# Guide_laser.net
KiCad netlist of a schematic drawn in Altium Designer
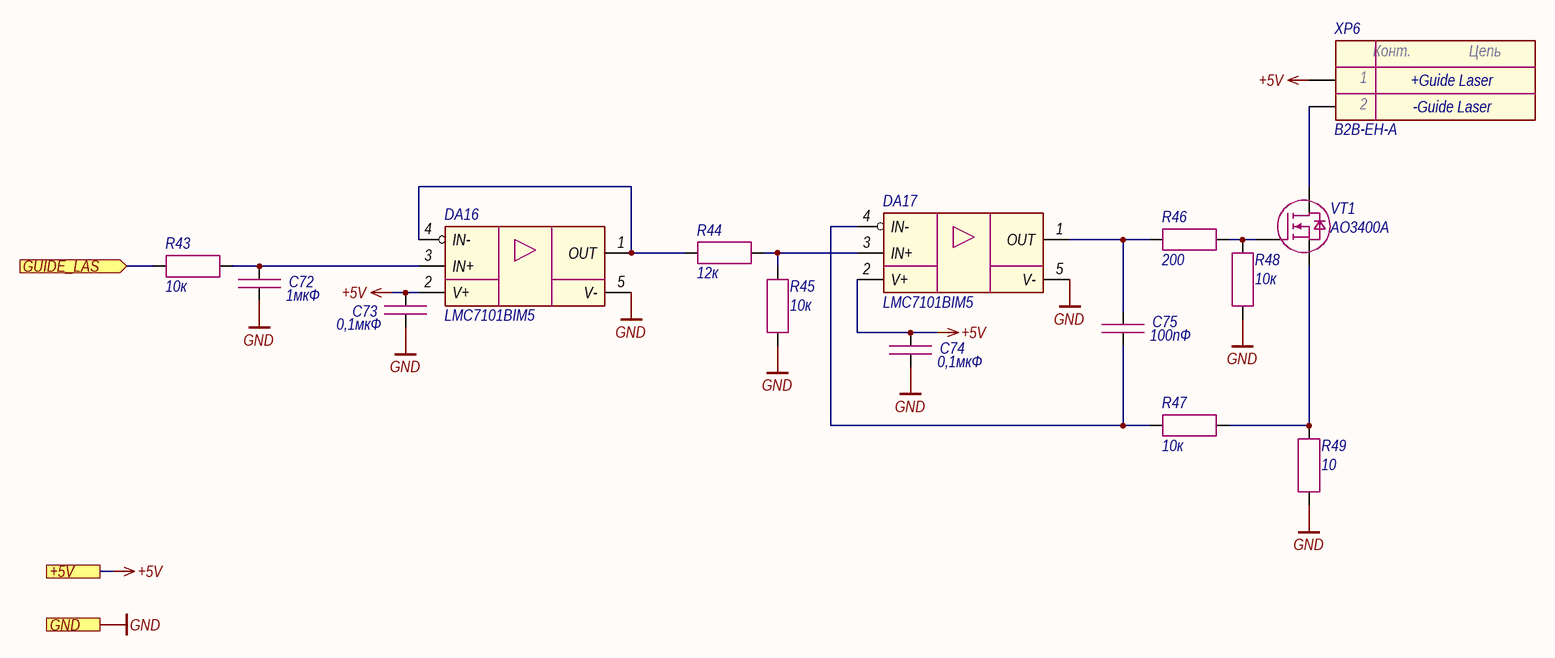
[diagram p0: Guide_laser.SchDoc]

(export (version "E")
  (design (tool "Eeschema 10.0.6"))
  (components
    (comp (ref "C72")
      (value "1мкФ")
      (footprint "Pcb_library:CAP_0603")
      (fields (field (name "MANUFACTURER") "Murata"))
      (libsource (lib "Schem_library") (part "Capacitor"))
    )
    (comp (ref "C73")
      (value "0,1мкФ")
      (footprint "Pcb_library:CAP_0603")
      (fields (field (name "MANUFACTURER") "Murata"))
      (libsource (lib "Schem_library") (part "Capacitor"))
    )
    (comp (ref "C74")
      (value "0,1мкФ")
      (footprint "Pcb_library:CAP_0603")
      (fields (field (name "MANUFACTURER") "Murata"))
      (libsource (lib "Schem_library") (part "Capacitor"))
    )
    (comp (ref "C75")
      (value "100пФ")
      (footprint "Pcb_library:CAP_0603")
      (fields (field (name "MANUFACTURER") "Murata"))
      (libsource (lib "Schem_library") (part "Capacitor"))
    )
    (comp (ref "DA16")
      (value "LMC7101BIM5")
      (footprint "Pcb_library:SOT-23-5")
      (fields (field (name "MANUFACTURER") "Texas Instruments"))
      (libsource (lib "Schem_library") (part "LMC7101"))
    )
    (comp (ref "DA17")
      (value "LMC7101BIM5")
      (footprint "Pcb_library:SOT-23-5")
      (fields (field (name "MANUFACTURER") "Texas Instruments"))
      (libsource (lib "Schem_library") (part "LMC7101"))
    )
    (comp (ref "R43")
      (value "10к")
      (footprint "Pcb_library:RES_0603")
      (fields (field (name "MANUFACTURER") "Yageo"))
      (libsource (lib "Schem_library") (part "Resistor"))
    )
    (comp (ref "R44")
      (value "12к")
      (footprint "Pcb_library:RES_0603")
      (fields (field (name "MANUFACTURER") "Yageo"))
      (libsource (lib "Schem_library") (part "Resistor"))
    )
    (comp (ref "R45")
      (value "10к")
      (footprint "Pcb_library:RES_0603")
      (fields (field (name "MANUFACTURER") "Yageo"))
      (libsource (lib "Schem_library") (part "Resistor"))
    )
    (comp (ref "R46")
      (value "200")
      (footprint "Pcb_library:RES_0603")
      (fields (field (name "MANUFACTURER") "Yageo"))
      (libsource (lib "Schem_library") (part "Resistor"))
    )
    (comp (ref "R47")
      (value "10к")
      (footprint "Pcb_library:RES_0603")
      (fields (field (name "MANUFACTURER") "Yageo"))
      (libsource (lib "Schem_library") (part "Resistor"))
    )
    (comp (ref "R48")
      (value "10к")
      (footprint "Pcb_library:RES_0603")
      (fields (field (name "MANUFACTURER") "Yageo"))
      (libsource (lib "Schem_library") (part "Resistor"))
    )
    (comp (ref "R49")
      (value "10")
      (footprint "Pcb_library:RES_1210")
      (fields (field (name "MANUFACTURER") "Yageo"))
      (libsource (lib "Schem_library") (part "Resistor"))
    )
    (comp (ref "VT1")
      (value "AO3400A")
      (footprint "Pcb_library:SOT-23-3")
      (fields (field (name "MANUFACTURER") "UMW"))
      (libsource (lib "Schem_library") (part "MOSFET N-channel"))
    )
    (comp (ref "XP6")
      (value "B2B-EH-A")
      (footprint "Pcb_library:B2B-EH-A")
      (fields (field (name "MANUFACTURER") "JST"))
      (libsource (lib "Schem_library") (part "Connector-2"))
    )
  )
  (nets
    (net (code "1") (name "+5V") (class "Default")
      (node (ref "C73") (pin "1") (pinfunction "1_1") (pintype "passive"))
      (node (ref "C74") (pin "1") (pinfunction "1_1") (pintype "passive"))
      (node (ref "DA16") (pin "2") (pinfunction "V+_2") (pintype "passive"))
      (node (ref "DA17") (pin "2") (pinfunction "V+_2") (pintype "passive"))
      (node (ref "XP6") (pin "1") (pintype "passive"))
    )
    (net (code "2") (name "/GUIDE_LAS") (class "Default")
      (node (ref "R43") (pin "1") (pinfunction "1_1") (pintype "passive"))
    )
    (net (code "3") (name "GND") (class "Default")
      (node (ref "C72") (pin "2") (pinfunction "2_2") (pintype "passive"))
      (node (ref "C73") (pin "2") (pinfunction "2_2") (pintype "passive"))
      (node (ref "C74") (pin "2") (pinfunction "2_2") (pintype "passive"))
      (node (ref "DA16") (pin "5") (pinfunction "V-_5") (pintype "passive"))
      (node (ref "DA17") (pin "5") (pinfunction "V-_5") (pintype "passive"))
      (node (ref "R45") (pin "2") (pinfunction "2_2") (pintype "passive"))
      (node (ref "R48") (pin "1") (pinfunction "1_1") (pintype "passive"))
      (node (ref "R49") (pin "1") (pinfunction "1_1") (pintype "passive"))
    )
    (net (code "4") (name "Net-(DA16-IN+)") (class "Default")
      (node (ref "C72") (pin "1") (pinfunction "1_1") (pintype "passive"))
      (node (ref "DA16") (pin "3") (pinfunction "IN+_3") (pintype "passive"))
      (node (ref "R43") (pin "2") (pinfunction "2_2") (pintype "passive"))
    )
    (net (code "5") (name "Net-(DA16-IN-)") (class "Default")
      (node (ref "DA16") (pin "1") (pinfunction "OUT_1") (pintype "passive"))
      (node (ref "DA16") (pin "4") (pinfunction "IN-_4") (pintype "passive"))
      (node (ref "R44") (pin "1") (pinfunction "1_1") (pintype "passive"))
    )
    (net (code "6") (name "Net-(DA17-IN+)") (class "Default")
      (node (ref "DA17") (pin "3") (pinfunction "IN+_3") (pintype "passive"))
      (node (ref "R44") (pin "2") (pinfunction "2_2") (pintype "passive"))
      (node (ref "R45") (pin "1") (pinfunction "1_1") (pintype "passive"))
    )
    (net (code "7") (name "Net-(DA17-IN-)") (class "Default")
      (node (ref "C75") (pin "2") (pinfunction "2_2") (pintype "passive"))
      (node (ref "DA17") (pin "4") (pinfunction "IN-_4") (pintype "passive"))
      (node (ref "R47") (pin "1") (pinfunction "1_1") (pintype "passive"))
    )
    (net (code "8") (name "Net-(DA17-OUT)") (class "Default")
      (node (ref "C75") (pin "1") (pinfunction "1_1") (pintype "passive"))
      (node (ref "DA17") (pin "1") (pinfunction "OUT_1") (pintype "passive"))
      (node (ref "R46") (pin "1") (pinfunction "1_1") (pintype "passive"))
    )
    (net (code "9") (name "Net-(VT1-D)") (class "Default")
      (node (ref "VT1") (pin "3") (pinfunction "D_3") (pintype "passive"))
      (node (ref "XP6") (pin "2") (pintype "passive"))
    )
    (net (code "10") (name "Net-(VT1-G)") (class "Default")
      (node (ref "R46") (pin "2") (pinfunction "2_2") (pintype "passive"))
      (node (ref "R48") (pin "2") (pinfunction "2_2") (pintype "passive"))
      (node (ref "VT1") (pin "1") (pinfunction "G_1") (pintype "passive"))
    )
    (net (code "11") (name "Net-(VT1-S)") (class "Default")
      (node (ref "R47") (pin "2") (pinfunction "2_2") (pintype "passive"))
      (node (ref "R49") (pin "2") (pinfunction "2_2") (pintype "passive"))
      (node (ref "VT1") (pin "2") (pinfunction "S_2") (pintype "passive"))
    )
  )
)
